# top.net
KiCad netlist of a schematic drawn in Altium Designer
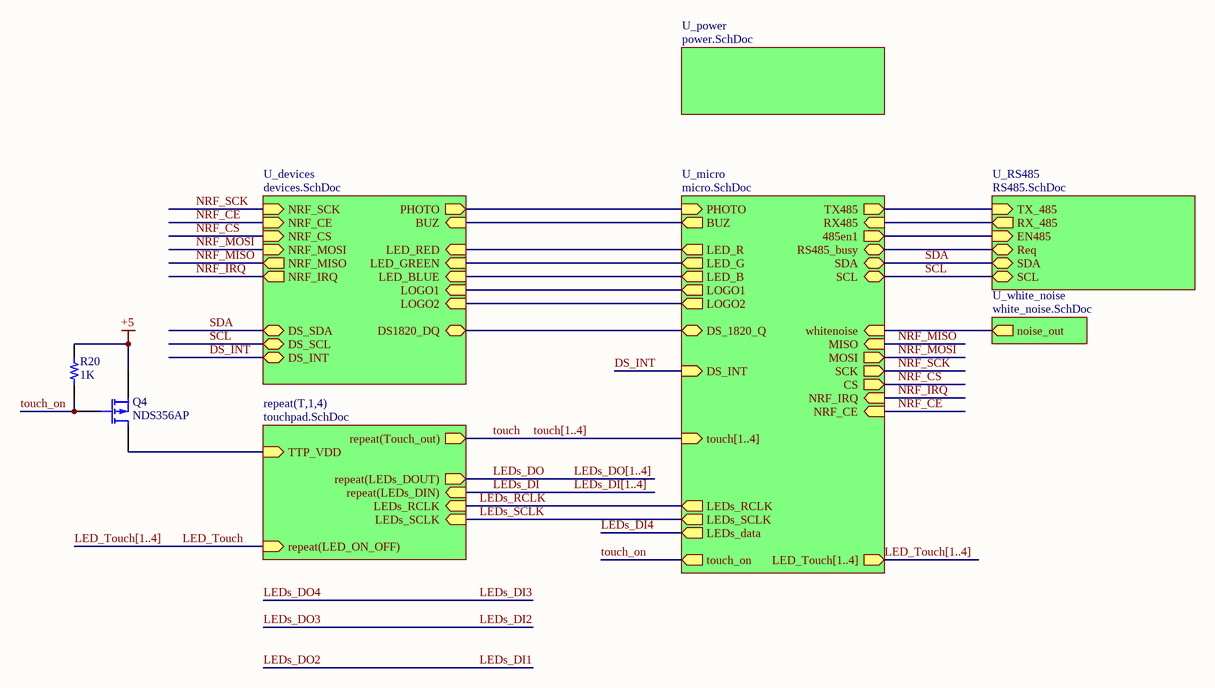
[diagram p0: top.SchDoc]

(export (version "E")
  (design (tool "Eeschema 10.0.6"))
  (components
    (comp (ref "Q4")
      (value "NDS356AP")
      (footprint "soT95p280x130-3n")
      (description "P-Channel MOSFET SOT23")
      (fields (field (name "PUBLISHER") "Altium Limited"))
      (libsource (lib "Miscellaneous Devices") (part "MOSFET-P"))
    )
    (comp (ref "R20")
      (value "1K")
      (footprint "0603R")
      (description "RES SMD 0603")
      (fields (field (name "PART NUMBER") "RCS0805100KFKEA"))
      (libsource (lib "lamp control-ver2") (part "Resistor"))
    )
  )
  (nets
    (net (code "6") (name "+5") (class "Default")
      (node (ref "Q4") (pin "3") (pinfunction "S_3") (pintype "passive"))
      (node (ref "R20") (pin "1") (pinfunction "1_1") (pintype "passive"))
    )
    (net (code "39") (name "/TTP_VDD") (class "Default")
      (node (ref "Q4") (pin "1") (pinfunction "D_1") (pintype "passive"))
    )
    (net (code "43") (name "/touch_on") (class "Default")
      (node (ref "Q4") (pin "2") (pinfunction "G_2") (pintype "passive"))
      (node (ref "R20") (pin "2") (pinfunction "2_2") (pintype "passive"))
    )
  )
)
